# linistepper_with_aligned_transistors_my_.net
KiCad netlist of a schematic drawn in EAGLE
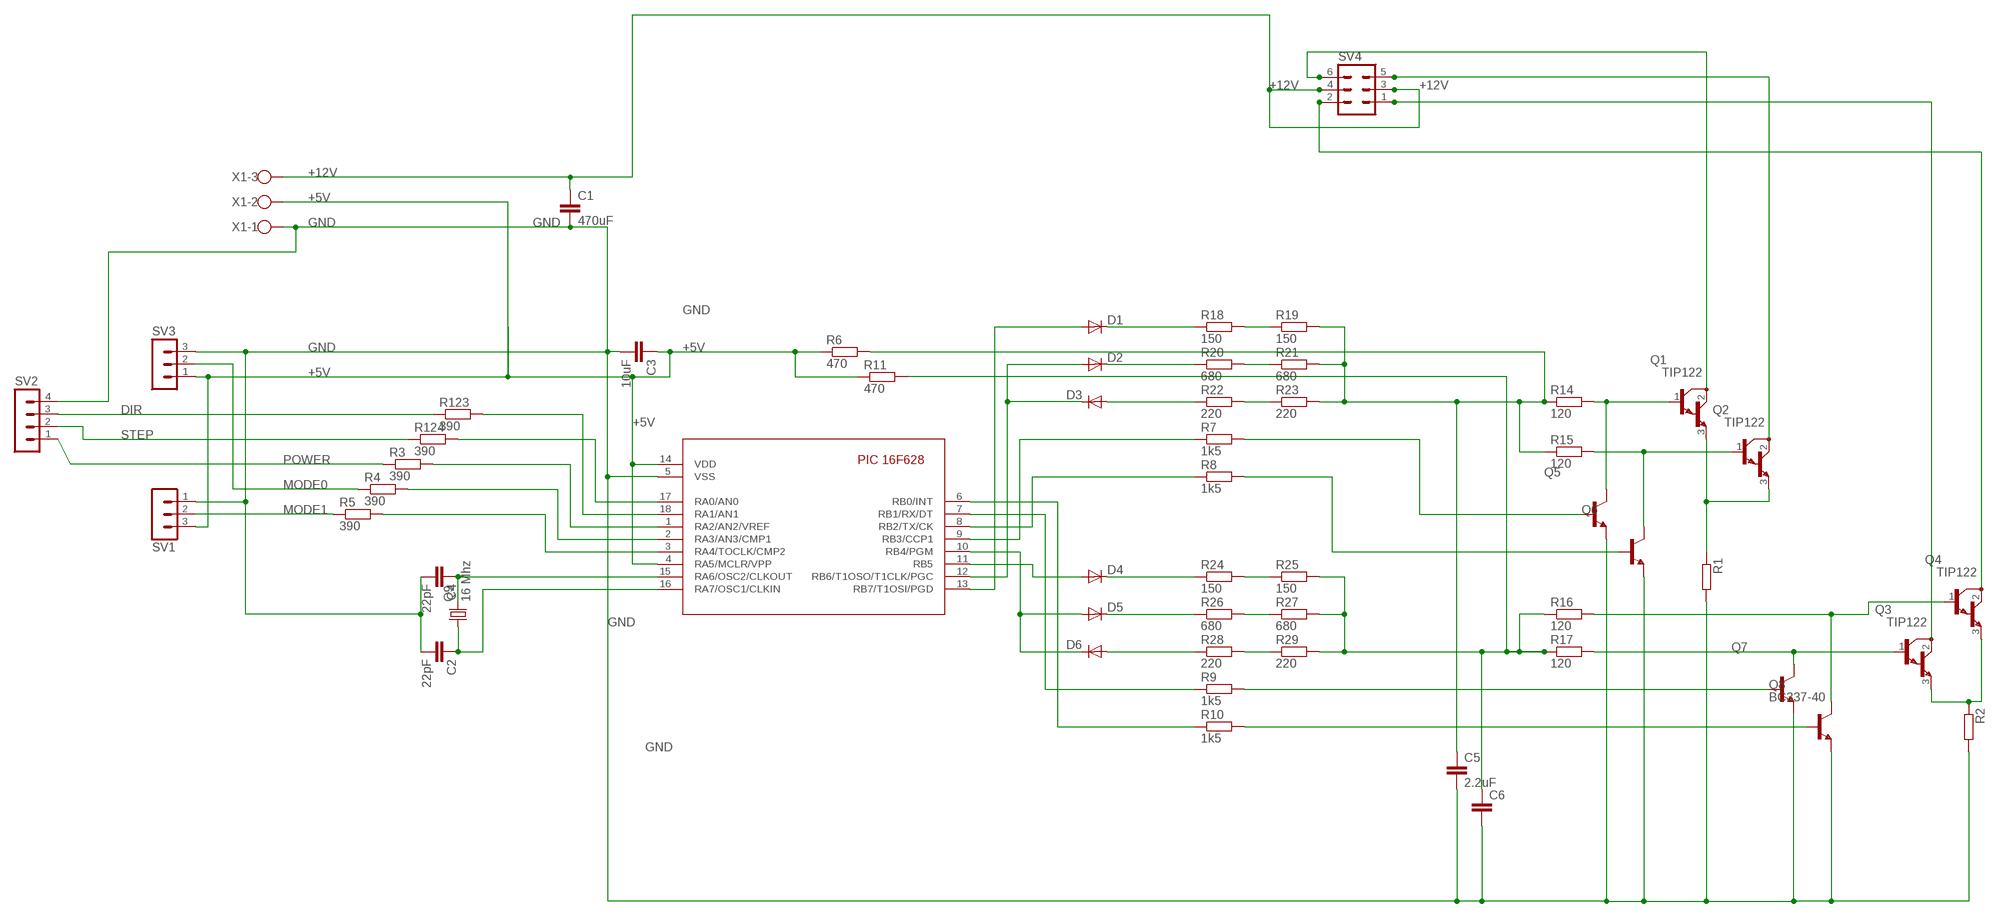
[diagram p0: schematic, sheet 1]

(export (version "E")
  (design (tool "Eeschema 10.0.6"))
  (components
    (comp (ref "C1")
      (value "470uF")
      (footprint "eagle-import:C050-045X075")
      (libsource (lib "eagle-import") (part "C-EU050-045X075"))
    )
    (comp (ref "C2")
      (value "22pF")
      (footprint "eagle-import:C025-024X044")
      (libsource (lib "eagle-import") (part "C-EU025-024X044"))
    )
    (comp (ref "C3")
      (value "10uF")
      (footprint "eagle-import:C025-040X050")
      (libsource (lib "eagle-import") (part "C-EU025-040X050"))
    )
    (comp (ref "C4")
      (value "22pF")
      (footprint "eagle-import:C025-024X044")
      (libsource (lib "eagle-import") (part "C-EU025-024X044"))
    )
    (comp (ref "C5")
      (value "2.2uF")
      (footprint "eagle-import:C050-024X044")
      (libsource (lib "eagle-import") (part "C-EU050-024X044"))
    )
    (comp (ref "C6")
      (value "C-EU050-024X044")
      (footprint "eagle-import:C050-024X044")
      (libsource (lib "eagle-import") (part "C-EU050-024X044"))
    )
    (comp (ref "D1")
      (value "1N4148")
      (footprint "eagle-import:DO35-10")
      (libsource (lib "eagle-import") (part "1N4148"))
    )
    (comp (ref "D2")
      (value "1N4148")
      (footprint "eagle-import:DO35-10")
      (libsource (lib "eagle-import") (part "1N4148"))
    )
    (comp (ref "D3")
      (value "1N4148")
      (footprint "eagle-import:DO35-10")
      (libsource (lib "eagle-import") (part "1N4148"))
    )
    (comp (ref "D4")
      (value "1N4148")
      (footprint "eagle-import:DO35-10")
      (libsource (lib "eagle-import") (part "1N4148"))
    )
    (comp (ref "D5")
      (value "1N4148")
      (footprint "eagle-import:DO35-10")
      (libsource (lib "eagle-import") (part "1N4148"))
    )
    (comp (ref "D6")
      (value "1N4148")
      (footprint "eagle-import:DO35-10")
      (libsource (lib "eagle-import") (part "1N4148"))
    )
    (comp (ref "Q1")
      (value "TIP122")
      (footprint "eagle-import:TO220")
      (libsource (lib "eagle-import") (part "TIP122"))
    )
    (comp (ref "Q2")
      (value "TIP122")
      (footprint "eagle-import:TO220")
      (libsource (lib "eagle-import") (part "TIP122"))
    )
    (comp (ref "Q3")
      (value "TIP122")
      (footprint "eagle-import:TO220")
      (libsource (lib "eagle-import") (part "TIP122"))
    )
    (comp (ref "Q4")
      (value "TIP122")
      (footprint "eagle-import:TO220")
      (libsource (lib "eagle-import") (part "TIP122"))
    )
    (comp (ref "Q5")
      (value "BC337-40")
      (footprint "eagle-import:TO92")
      (libsource (lib "eagle-import") (part "BC337-40"))
    )
    (comp (ref "Q6")
      (value "BC337-40")
      (footprint "eagle-import:TO92")
      (libsource (lib "eagle-import") (part "BC337-40"))
    )
    (comp (ref "Q7")
      (value "BC337-40")
      (footprint "eagle-import:TO92")
      (libsource (lib "eagle-import") (part "BC337-40"))
    )
    (comp (ref "Q8")
      (value "BC337-40")
      (footprint "eagle-import:TO92")
      (libsource (lib "eagle-import") (part "BC337-40"))
    )
    (comp (ref "Q9")
      (value "16 Mhz")
      (footprint "eagle-import:HC49_S")
      (libsource (lib "eagle-import") (part "CRYTALHC49S"))
    )
    (comp (ref "R1")
      (value "R-EU_0922/22")
      (footprint "eagle-import:0922_22")
      (libsource (lib "eagle-import") (part "R-EU_0922/22"))
    )
    (comp (ref "R2")
      (value "R-EU_0922/22")
      (footprint "eagle-import:0922_22")
      (libsource (lib "eagle-import") (part "R-EU_0922/22"))
    )
    (comp (ref "R3")
      (value "390")
      (footprint "eagle-import:0204_7")
      (libsource (lib "eagle-import") (part "R-EU_0204/7"))
    )
    (comp (ref "R4")
      (value "390")
      (footprint "eagle-import:0204_7")
      (libsource (lib "eagle-import") (part "R-EU_0204/7"))
    )
    (comp (ref "R5")
      (value "390")
      (footprint "eagle-import:0207_5V")
      (libsource (lib "eagle-import") (part "R-EU_0207/5V"))
    )
    (comp (ref "R6")
      (value "470")
      (footprint "eagle-import:0207_10")
      (libsource (lib "eagle-import") (part "R-EU_0207/10"))
    )
    (comp (ref "R7")
      (value "1k5")
      (footprint "eagle-import:0207_10")
      (libsource (lib "eagle-import") (part "R-EU_0207/10"))
    )
    (comp (ref "R8")
      (value "1k5")
      (footprint "eagle-import:0207_10")
      (libsource (lib "eagle-import") (part "R-EU_0207/10"))
    )
    (comp (ref "R9")
      (value "1k5")
      (footprint "eagle-import:0207_7")
      (libsource (lib "eagle-import") (part "resistor_R-EU_0207/7"))
    )
    (comp (ref "R10")
      (value "1k5")
      (footprint "eagle-import:0207_5V")
      (libsource (lib "eagle-import") (part "resistor_R-EU_0207/5V"))
    )
    (comp (ref "R11")
      (value "470")
      (footprint "eagle-import:0207_7")
      (libsource (lib "eagle-import") (part "resistor_R-EU_0207/7"))
    )
    (comp (ref "R14")
      (value "120")
      (footprint "eagle-import:0207_10")
      (libsource (lib "eagle-import") (part "R-EU_0207/10"))
    )
    (comp (ref "R15")
      (value "120")
      (footprint "eagle-import:0207_10")
      (libsource (lib "eagle-import") (part "R-EU_0207/10"))
    )
    (comp (ref "R16")
      (value "120")
      (footprint "eagle-import:0207_5V")
      (libsource (lib "eagle-import") (part "resistor_R-EU_0207/5V"))
    )
    (comp (ref "R17")
      (value "120")
      (footprint "eagle-import:0207_7")
      (libsource (lib "eagle-import") (part "resistor_R-EU_0207/7"))
    )
    (comp (ref "R18")
      (value "150")
      (footprint "eagle-import:0207_2V")
      (libsource (lib "eagle-import") (part "R-EU_0207/2V"))
    )
    (comp (ref "R19")
      (value "150")
      (footprint "eagle-import:0207_2V")
      (libsource (lib "eagle-import") (part "R-EU_0207/2V"))
    )
    (comp (ref "R20")
      (value "680")
      (footprint "eagle-import:0207_2V")
      (libsource (lib "eagle-import") (part "R-EU_0207/2V"))
    )
    (comp (ref "R21")
      (value "680")
      (footprint "eagle-import:0207_2V")
      (libsource (lib "eagle-import") (part "R-EU_0207/2V"))
    )
    (comp (ref "R22")
      (value "220")
      (footprint "eagle-import:0207_2V")
      (libsource (lib "eagle-import") (part "R-EU_0207/2V"))
    )
    (comp (ref "R23")
      (value "220")
      (footprint "eagle-import:0207_2V")
      (libsource (lib "eagle-import") (part "R-EU_0207/2V"))
    )
    (comp (ref "R24")
      (value "150")
      (footprint "eagle-import:0207_2V")
      (libsource (lib "eagle-import") (part "R-EU_0207/2V"))
    )
    (comp (ref "R25")
      (value "150")
      (footprint "eagle-import:0207_2V")
      (libsource (lib "eagle-import") (part "R-EU_0207/2V"))
    )
    (comp (ref "R26")
      (value "680")
      (footprint "eagle-import:0207_2V")
      (libsource (lib "eagle-import") (part "R-EU_0207/2V"))
    )
    (comp (ref "R27")
      (value "680")
      (footprint "eagle-import:0207_2V")
      (libsource (lib "eagle-import") (part "R-EU_0207/2V"))
    )
    (comp (ref "R28")
      (value "220")
      (footprint "eagle-import:0207_2V")
      (libsource (lib "eagle-import") (part "R-EU_0207/2V"))
    )
    (comp (ref "R29")
      (value "220")
      (footprint "eagle-import:0207_2V")
      (libsource (lib "eagle-import") (part "R-EU_0207/2V"))
    )
    (comp (ref "R123")
      (value "390")
      (footprint "eagle-import:0207_2V")
      (libsource (lib "eagle-import") (part "R-EU_0207/2V"))
    )
    (comp (ref "R124")
      (value "390")
      (footprint "eagle-import:0207_2V")
      (libsource (lib "eagle-import") (part "R-EU_0207/2V"))
    )
    (comp (ref "SV1")
      (value "MA03-1")
      (footprint "eagle-import:MA03-1")
      (libsource (lib "eagle-import") (part "MA03-1"))
    )
    (comp (ref "SV2")
      (value "MA04-1")
      (footprint "eagle-import:MA04-1")
      (libsource (lib "eagle-import") (part "MA04-1"))
    )
    (comp (ref "SV3")
      (value "MA03-1")
      (footprint "eagle-import:MA03-1")
      (libsource (lib "eagle-import") (part "MA03-1"))
    )
    (comp (ref "SV4")
      (value "MA03-2")
      (footprint "eagle-import:MA03-2")
      (libsource (lib "eagle-import") (part "MA03-2"))
    )
    (comp (ref "U$1")
      (value "16F628")
      (footprint "eagle-import:PIC16F628-18-LEAD-PDIP")
      (libsource (lib "eagle-import") (part "16F628"))
    )
    (comp (ref "X1")
      (value "W237-103")
      (footprint "eagle-import:W237-103")
      (libsource (lib "eagle-import") (part "W237-103"))
    )
  )
  (nets
    (net (code "1") (name "/+5V") (class "Default")
      (node (ref "C3") (pin "1") (pinfunction "1_1") (pintype "passive"))
      (node (ref "R11") (pin "1") (pinfunction "1_1") (pintype "passive"))
      (node (ref "R6") (pin "1") (pinfunction "1_1") (pintype "passive"))
      (node (ref "SV1") (pin "3") (pinfunction "3_3") (pintype "passive"))
      (node (ref "SV3") (pin "1") (pinfunction "1_1") (pintype "passive"))
      (node (ref "U$1") (pin "14") (pinfunction "VDD_14") (pintype "input"))
      (node (ref "U$1") (pin "4") (pinfunction "RA5/MCLR/VPP_4") (pintype "bidirectional"))
      (node (ref "X1") (pin "2") (pinfunction "KL_2") (pintype "passive"))
    )
    (net (code "2") (name "/+12V") (class "Default")
      (node (ref "C1") (pin "1") (pinfunction "1_1") (pintype "passive"))
      (node (ref "SV4") (pin "3") (pinfunction "3_3") (pintype "passive"))
      (node (ref "SV4") (pin "4") (pinfunction "4_4") (pintype "passive"))
      (node (ref "X1") (pin "3") (pinfunction "KL_3") (pintype "passive"))
    )
    (net (code "3") (name "/DIR") (class "Default")
      (node (ref "R123") (pin "1") (pinfunction "1_1") (pintype "passive"))
      (node (ref "SV2") (pin "3") (pinfunction "3_3") (pintype "passive"))
    )
    (net (code "4") (name "/GND") (class "Default")
      (node (ref "C1") (pin "2") (pinfunction "2_2") (pintype "passive"))
      (node (ref "C2") (pin "2") (pinfunction "2_2") (pintype "passive"))
      (node (ref "C3") (pin "2") (pinfunction "2_2") (pintype "passive"))
      (node (ref "C4") (pin "2") (pinfunction "2_2") (pintype "passive"))
      (node (ref "C5") (pin "2") (pinfunction "2_2") (pintype "passive"))
      (node (ref "C6") (pin "2") (pinfunction "2_2") (pintype "passive"))
      (node (ref "Q5") (pin "1") (pinfunction "E_1") (pintype "passive"))
      (node (ref "Q6") (pin "1") (pinfunction "E_1") (pintype "passive"))
      (node (ref "Q7") (pin "1") (pinfunction "E_1") (pintype "passive"))
      (node (ref "Q8") (pin "1") (pinfunction "E_1") (pintype "passive"))
      (node (ref "R1") (pin "2") (pinfunction "2_2") (pintype "passive"))
      (node (ref "R2") (pin "2") (pinfunction "2_2") (pintype "passive"))
      (node (ref "SV1") (pin "1") (pinfunction "1_1") (pintype "passive"))
      (node (ref "SV2") (pin "4") (pinfunction "4_4") (pintype "passive"))
      (node (ref "SV3") (pin "3") (pinfunction "3_3") (pintype "passive"))
      (node (ref "U$1") (pin "5") (pinfunction "VSS_5") (pintype "input"))
      (node (ref "X1") (pin "1") (pinfunction "KL_1") (pintype "passive"))
    )
    (net (code "5") (name "/MODE0") (class "Default")
      (node (ref "R4") (pin "1") (pinfunction "1_1") (pintype "passive"))
      (node (ref "SV3") (pin "2") (pinfunction "2_2") (pintype "passive"))
    )
    (net (code "6") (name "/MODE1") (class "Default")
      (node (ref "R5") (pin "1") (pinfunction "1_1") (pintype "passive"))
      (node (ref "SV1") (pin "2") (pinfunction "2_2") (pintype "passive"))
    )
    (net (code "7") (name "/POWER") (class "Default")
      (node (ref "R3") (pin "1") (pinfunction "1_1") (pintype "passive"))
      (node (ref "SV2") (pin "1") (pinfunction "1_1") (pintype "passive"))
    )
    (net (code "8") (name "/STEP") (class "Default")
      (node (ref "R124") (pin "1") (pinfunction "1_1") (pintype "passive"))
      (node (ref "SV2") (pin "2") (pinfunction "2_2") (pintype "passive"))
    )
    (net (code "9") (name "Net-(C5-Pad1)") (class "Default")
      (node (ref "C5") (pin "1") (pinfunction "1_1") (pintype "passive"))
      (node (ref "R14") (pin "1") (pinfunction "1_1") (pintype "passive"))
      (node (ref "R15") (pin "1") (pinfunction "1_1") (pintype "passive"))
      (node (ref "R19") (pin "2") (pinfunction "2_2") (pintype "passive"))
      (node (ref "R21") (pin "2") (pinfunction "2_2") (pintype "passive"))
      (node (ref "R23") (pin "2") (pinfunction "2_2") (pintype "passive"))
      (node (ref "R6") (pin "2") (pinfunction "2_2") (pintype "passive"))
    )
    (net (code "10") (name "Net-(C6-Pad1)") (class "Default")
      (node (ref "C6") (pin "1") (pinfunction "1_1") (pintype "passive"))
      (node (ref "R11") (pin "2") (pinfunction "2_2") (pintype "passive"))
      (node (ref "R16") (pin "1") (pinfunction "1_1") (pintype "passive"))
      (node (ref "R17") (pin "1") (pinfunction "1_1") (pintype "passive"))
      (node (ref "R25") (pin "2") (pinfunction "2_2") (pintype "passive"))
      (node (ref "R27") (pin "2") (pinfunction "2_2") (pintype "passive"))
      (node (ref "R29") (pin "2") (pinfunction "2_2") (pintype "passive"))
    )
    (net (code "11") (name "Net-(D1-PadC)") (class "Default")
      (node (ref "D1") (pin "C") (pinfunction "C_C") (pintype "passive"))
      (node (ref "R18") (pin "1") (pinfunction "1_1") (pintype "passive"))
    )
    (net (code "12") (name "Net-(D2-PadC)") (class "Default")
      (node (ref "D2") (pin "C") (pinfunction "C_C") (pintype "passive"))
      (node (ref "R20") (pin "1") (pinfunction "1_1") (pintype "passive"))
    )
    (net (code "13") (name "Net-(D3-PadA)") (class "Default")
      (node (ref "D3") (pin "A") (pinfunction "A_A") (pintype "passive"))
      (node (ref "R22") (pin "1") (pinfunction "1_1") (pintype "passive"))
    )
    (net (code "14") (name "Net-(D4-PadC)") (class "Default")
      (node (ref "D4") (pin "C") (pinfunction "C_C") (pintype "passive"))
      (node (ref "R24") (pin "1") (pinfunction "1_1") (pintype "passive"))
    )
    (net (code "15") (name "Net-(D5-PadC)") (class "Default")
      (node (ref "D5") (pin "C") (pinfunction "C_C") (pintype "passive"))
      (node (ref "R26") (pin "1") (pinfunction "1_1") (pintype "passive"))
    )
    (net (code "16") (name "Net-(D6-PadA)") (class "Default")
      (node (ref "D6") (pin "A") (pinfunction "A_A") (pintype "passive"))
      (node (ref "R28") (pin "1") (pinfunction "1_1") (pintype "passive"))
    )
    (net (code "17") (name "Net-(Q1-B)") (class "Default")
      (node (ref "Q1") (pin "1") (pinfunction "B_1") (pintype "passive"))
      (node (ref "Q5") (pin "3") (pinfunction "C_3") (pintype "passive"))
      (node (ref "R14") (pin "2") (pinfunction "2_2") (pintype "passive"))
    )
    (net (code "18") (name "Net-(Q1-C)") (class "Default")
      (node (ref "Q1") (pin "2") (pinfunction "C_2") (pintype "passive"))
      (node (ref "SV4") (pin "6") (pinfunction "6_6") (pintype "passive"))
    )
    (net (code "19") (name "Net-(Q1-E)") (class "Default")
      (node (ref "Q1") (pin "3") (pinfunction "E_3") (pintype "passive"))
      (node (ref "Q2") (pin "3") (pinfunction "E_3") (pintype "passive"))
      (node (ref "R1") (pin "1") (pinfunction "1_1") (pintype "passive"))
    )
    (net (code "20") (name "Net-(Q2-B)") (class "Default")
      (node (ref "Q2") (pin "1") (pinfunction "B_1") (pintype "passive"))
      (node (ref "Q6") (pin "3") (pinfunction "C_3") (pintype "passive"))
      (node (ref "R15") (pin "2") (pinfunction "2_2") (pintype "passive"))
    )
    (net (code "21") (name "Net-(Q2-C)") (class "Default")
      (node (ref "Q2") (pin "2") (pinfunction "C_2") (pintype "passive"))
      (node (ref "SV4") (pin "5") (pinfunction "5_5") (pintype "passive"))
    )
    (net (code "22") (name "Net-(Q3-B)") (class "Default")
      (node (ref "Q3") (pin "1") (pinfunction "B_1") (pintype "passive"))
      (node (ref "Q7") (pin "3") (pinfunction "C_3") (pintype "passive"))
      (node (ref "R17") (pin "2") (pinfunction "2_2") (pintype "passive"))
    )
    (net (code "23") (name "Net-(Q3-C)") (class "Default")
      (node (ref "Q3") (pin "2") (pinfunction "C_2") (pintype "passive"))
      (node (ref "SV4") (pin "1") (pinfunction "1_1") (pintype "passive"))
    )
    (net (code "24") (name "Net-(Q3-E)") (class "Default")
      (node (ref "Q3") (pin "3") (pinfunction "E_3") (pintype "passive"))
      (node (ref "Q4") (pin "3") (pinfunction "E_3") (pintype "passive"))
      (node (ref "R2") (pin "1") (pinfunction "1_1") (pintype "passive"))
    )
    (net (code "25") (name "Net-(Q4-B)") (class "Default")
      (node (ref "Q4") (pin "1") (pinfunction "B_1") (pintype "passive"))
      (node (ref "Q8") (pin "3") (pinfunction "C_3") (pintype "passive"))
      (node (ref "R16") (pin "2") (pinfunction "2_2") (pintype "passive"))
    )
    (net (code "26") (name "Net-(Q4-C)") (class "Default")
      (node (ref "Q4") (pin "2") (pinfunction "C_2") (pintype "passive"))
      (node (ref "SV4") (pin "2") (pinfunction "2_2") (pintype "passive"))
    )
    (net (code "27") (name "Net-(Q5-B)") (class "Default")
      (node (ref "Q5") (pin "2") (pinfunction "B_2") (pintype "passive"))
      (node (ref "R7") (pin "2") (pinfunction "2_2") (pintype "passive"))
    )
    (net (code "28") (name "Net-(Q6-B)") (class "Default")
      (node (ref "Q6") (pin "2") (pinfunction "B_2") (pintype "passive"))
      (node (ref "R8") (pin "2") (pinfunction "2_2") (pintype "passive"))
    )
    (net (code "29") (name "Net-(Q7-B)") (class "Default")
      (node (ref "Q7") (pin "2") (pinfunction "B_2") (pintype "passive"))
      (node (ref "R9") (pin "2") (pinfunction "2_2") (pintype "passive"))
    )
    (net (code "30") (name "Net-(Q8-B)") (class "Default")
      (node (ref "Q8") (pin "2") (pinfunction "B_2") (pintype "passive"))
      (node (ref "R10") (pin "2") (pinfunction "2_2") (pintype "passive"))
    )
    (net (code "31") (name "Net-(R18-Pad2)") (class "Default")
      (node (ref "R18") (pin "2") (pinfunction "2_2") (pintype "passive"))
      (node (ref "R19") (pin "1") (pinfunction "1_1") (pintype "passive"))
    )
    (net (code "32") (name "Net-(R20-Pad2)") (class "Default")
      (node (ref "R20") (pin "2") (pinfunction "2_2") (pintype "passive"))
      (node (ref "R21") (pin "1") (pinfunction "1_1") (pintype "passive"))
    )
    (net (code "33") (name "Net-(R22-Pad2)") (class "Default")
      (node (ref "R22") (pin "2") (pinfunction "2_2") (pintype "passive"))
      (node (ref "R23") (pin "1") (pinfunction "1_1") (pintype "passive"))
    )
    (net (code "34") (name "Net-(R24-Pad2)") (class "Default")
      (node (ref "R24") (pin "2") (pinfunction "2_2") (pintype "passive"))
      (node (ref "R25") (pin "1") (pinfunction "1_1") (pintype "passive"))
    )
    (net (code "35") (name "Net-(R26-Pad2)") (class "Default")
      (node (ref "R26") (pin "2") (pinfunction "2_2") (pintype "passive"))
      (node (ref "R27") (pin "1") (pinfunction "1_1") (pintype "passive"))
    )
    (net (code "36") (name "Net-(R28-Pad2)") (class "Default")
      (node (ref "R28") (pin "2") (pinfunction "2_2") (pintype "passive"))
      (node (ref "R29") (pin "1") (pinfunction "1_1") (pintype "passive"))
    )
    (net (code "37") (name "Net-(U$1-RA0{slash}AN0)") (class "Default")
      (node (ref "R124") (pin "2") (pinfunction "2_2") (pintype "passive"))
      (node (ref "U$1") (pin "17") (pinfunction "RA0/AN0_17") (pintype "bidirectional"))
    )
    (net (code "38") (name "Net-(U$1-RA1{slash}AN1)") (class "Default")
      (node (ref "R123") (pin "2") (pinfunction "2_2") (pintype "passive"))
      (node (ref "U$1") (pin "18") (pinfunction "RA1/AN1_18") (pintype "bidirectional"))
    )
    (net (code "39") (name "Net-(U$1-RA2{slash}AN2{slash}VREF)") (class "Default")
      (node (ref "R3") (pin "2") (pinfunction "2_2") (pintype "passive"))
      (node (ref "U$1") (pin "1") (pinfunction "RA2/AN2/VREF_1") (pintype "bidirectional"))
    )
    (net (code "40") (name "Net-(U$1-RA3{slash}AN3{slash}CMP1)") (class "Default")
      (node (ref "R4") (pin "2") (pinfunction "2_2") (pintype "passive"))
      (node (ref "U$1") (pin "2") (pinfunction "RA3/AN3/CMP1_2") (pintype "bidirectional"))
    )
    (net (code "41") (name "Net-(U$1-RA4{slash}TOCLK{slash}CMP2)") (class "Default")
      (node (ref "R5") (pin "2") (pinfunction "2_2") (pintype "passive"))
      (node (ref "U$1") (pin "3") (pinfunction "RA4/TOCLK/CMP2_3") (pintype "bidirectional"))
    )
    (net (code "42") (name "Net-(U$1-RA6{slash}OSC2{slash}CLKOUT)") (class "Default")
      (node (ref "C4") (pin "1") (pinfunction "1_1") (pintype "passive"))
      (node (ref "Q9") (pin "2") (pinfunction "2_2") (pintype "passive"))
      (node (ref "U$1") (pin "15") (pinfunction "RA6/OSC2/CLKOUT_15") (pintype "bidirectional"))
    )
    (net (code "43") (name "Net-(U$1-RA7{slash}OSC1{slash}CLKIN)") (class "Default")
      (node (ref "C2") (pin "1") (pinfunction "1_1") (pintype "passive"))
      (node (ref "Q9") (pin "1") (pinfunction "1_1") (pintype "passive"))
      (node (ref "U$1") (pin "16") (pinfunction "RA7/OSC1/CLKIN_16") (pintype "bidirectional"))
    )
    (net (code "44") (name "Net-(U$1-RB0{slash}INT)") (class "Default")
      (node (ref "R10") (pin "1") (pinfunction "1_1") (pintype "passive"))
      (node (ref "U$1") (pin "6") (pinfunction "RB0/INT_6") (pintype "bidirectional"))
    )
    (net (code "45") (name "Net-(U$1-RB1{slash}RX{slash}DT)") (class "Default")
      (node (ref "R9") (pin "1") (pinfunction "1_1") (pintype "passive"))
      (node (ref "U$1") (pin "7") (pinfunction "RB1/RX/DT_7") (pintype "bidirectional"))
    )
    (net (code "46") (name "Net-(U$1-RB2{slash}TX{slash}CK)") (class "Default")
      (node (ref "R8") (pin "1") (pinfunction "1_1") (pintype "passive"))
      (node (ref "U$1") (pin "8") (pinfunction "RB2/TX/CK_8") (pintype "bidirectional"))
    )
    (net (code "47") (name "Net-(U$1-RB3{slash}CCP1)") (class "Default")
      (node (ref "R7") (pin "1") (pinfunction "1_1") (pintype "passive"))
      (node (ref "U$1") (pin "9") (pinfunction "RB3/CCP1_9") (pintype "bidirectional"))
    )
    (net (code "48") (name "Net-(U$1-RB4{slash}PGM)") (class "Default")
      (node (ref "D5") (pin "A") (pinfunction "A_A") (pintype "passive"))
      (node (ref "D6") (pin "C") (pinfunction "C_C") (pintype "passive"))
      (node (ref "U$1") (pin "10") (pinfunction "RB4/PGM_10") (pintype "bidirectional"))
    )
    (net (code "49") (name "Net-(U$1-RB5)") (class "Default")
      (node (ref "D4") (pin "A") (pinfunction "A_A") (pintype "passive"))
      (node (ref "U$1") (pin "11") (pinfunction "RB5_11") (pintype "bidirectional"))
    )
    (net (code "50") (name "Net-(U$1-RB6{slash}T1OSO{slash}T1CLK{slash}PGC)") (class "Default")
      (node (ref "D2") (pin "A") (pinfunction "A_A") (pintype "passive"))
      (node (ref "D3") (pin "C") (pinfunction "C_C") (pintype "passive"))
      (node (ref "U$1") (pin "12") (pinfunction "RB6/T1OSO/T1CLK/PGC_12") (pintype "bidirectional"))
    )
    (net (code "51") (name "Net-(U$1-RB7{slash}T1OSI{slash}PGD)") (class "Default")
      (node (ref "D1") (pin "A") (pinfunction "A_A") (pintype "passive"))
      (node (ref "U$1") (pin "13") (pinfunction "RB7/T1OSI/PGD_13") (pintype "bidirectional"))
    )
  )
)
